# Misc_switches.net
KiCad netlist of a schematic drawn in Altium Designer
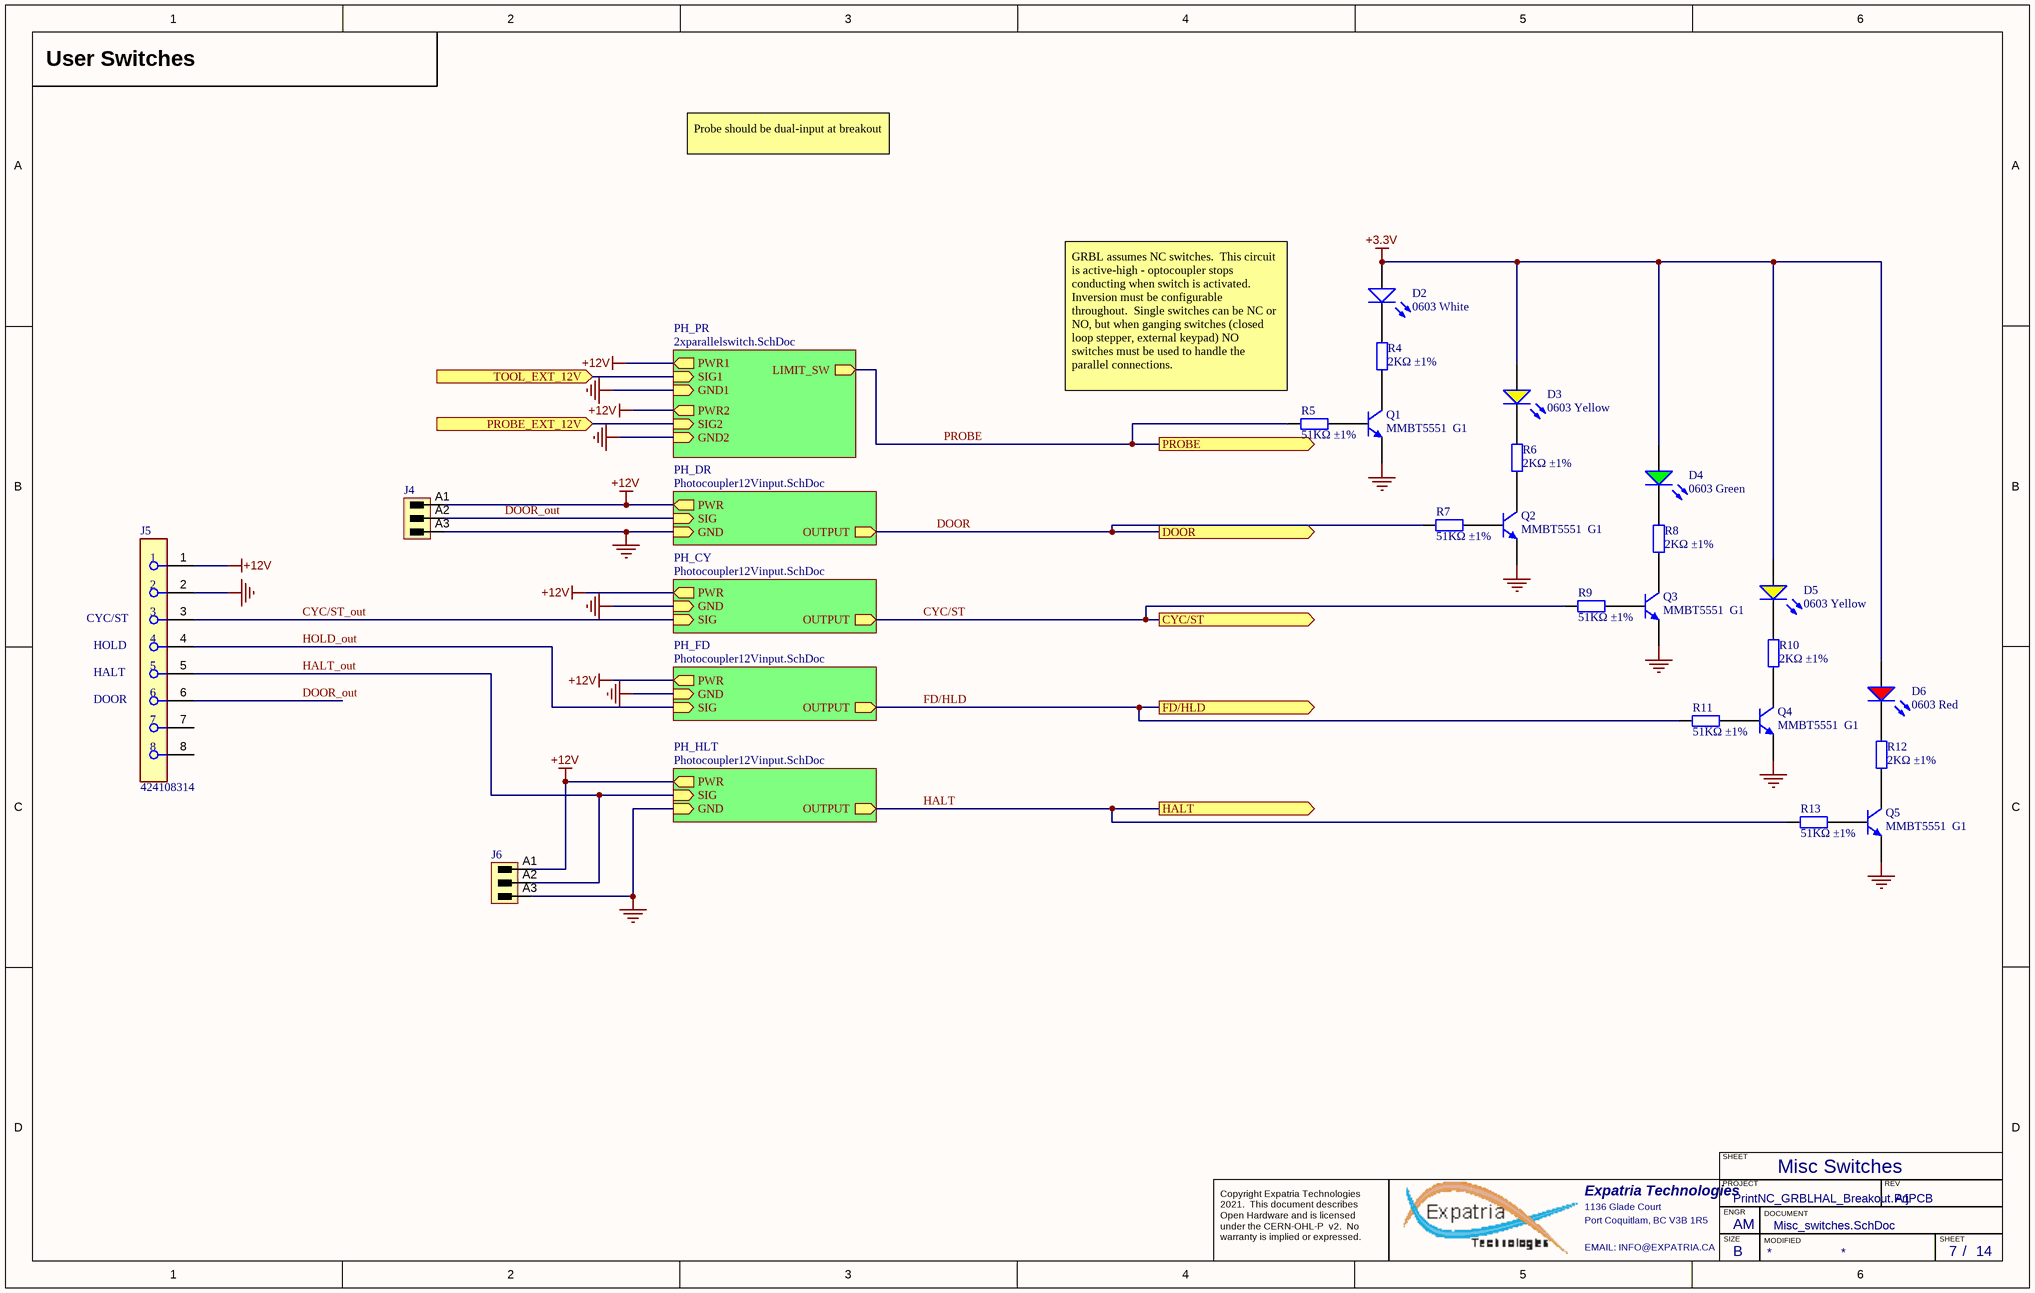
[diagram p0: Misc_switches.SchDoc]

(export (version "E")
  (design (tool "Eeschema 10.0.6"))
  (components
    (comp (ref "D2")
      (value "0603 White")
      (footprint "0603_LED_S1")
      (description "LED")
      (libsource (lib "LED") (part "0603 LED White"))
    )
    (comp (ref "D3")
      (value "0603 Yellow")
      (footprint "0603_LED_S1")
      (description "LED")
      (libsource (lib "LED") (part "0603 LED Yellow"))
    )
    (comp (ref "D4")
      (value "0603 Green")
      (footprint "0603_LED_S1")
      (description "LED")
      (libsource (lib "LED") (part "0603 LED Green"))
    )
    (comp (ref "D5")
      (value "0603 Yellow")
      (footprint "0603_LED_S1")
      (description "LED")
      (libsource (lib "LED") (part "0603 LED Yellow"))
    )
    (comp (ref "D6")
      (value "0603 Red")
      (footprint "0603_LED_S1")
      (description "LED")
      (libsource (lib "LED") (part "0603 LED Red"))
    )
    (comp (ref "J4")
      (value "~")
      (footprint "SL_3_50_180G_03")
      (fields
        (field (name "PARTNUMBER") "WJ15EDGVC-3.5-3P")
        (field (name "MANUFACTURER") "Ningbo Kangnex Elec")
      )
      (libsource (lib "PrintNC_GRBLHAL_Breakout") (part "Header_Male_03_1x03"))
    )
    (comp (ref "J5")
      (value "424108314")
      (footprint "FP-5555799-1-MFG")
      (description "CONN MOD JACK 8P8C VERT UNSHLD")
      (libsource (lib "PrintNC_GRBLHAL_Breakout") (part "a32a9c29f5c2290c50060dfb8ad7212"))
    )
    (comp (ref "J6")
      (value "~")
      (footprint "SL_3_50_180G_03")
      (fields
        (field (name "PARTNUMBER") "WJ15EDGVC-3.5-3P")
        (field (name "MANUFACTURER") "Ningbo Kangnex Elec")
      )
      (libsource (lib "PrintNC_GRBLHAL_Breakout") (part "Header_Male_03_1x03"))
    )
    (comp (ref "Q1")
      (value "MMBT5551  G1")
      (footprint "SOT-23(SOT-23-3)")
      (description "三极管")
      (libsource (lib "PrintNC_GRBLHAL_Breakout") (part "SOT-23 MMBT5551  G1"))
    )
    (comp (ref "Q2")
      (value "MMBT5551  G1")
      (footprint "SOT-23(SOT-23-3)")
      (description "三极管")
      (libsource (lib "PrintNC_GRBLHAL_Breakout") (part "SOT-23 MMBT5551  G1"))
    )
    (comp (ref "Q3")
      (value "MMBT5551  G1")
      (footprint "SOT-23(SOT-23-3)")
      (description "三极管")
      (libsource (lib "PrintNC_GRBLHAL_Breakout") (part "SOT-23 MMBT5551  G1"))
    )
    (comp (ref "Q4")
      (value "MMBT5551  G1")
      (footprint "SOT-23(SOT-23-3)")
      (description "三极管")
      (libsource (lib "PrintNC_GRBLHAL_Breakout") (part "SOT-23 MMBT5551  G1"))
    )
    (comp (ref "Q5")
      (value "MMBT5551  G1")
      (footprint "SOT-23(SOT-23-3)")
      (description "三极管")
      (libsource (lib "PrintNC_GRBLHAL_Breakout") (part "SOT-23 MMBT5551  G1"))
    )
    (comp (ref "R4")
      (value "2KΩ ±1%")
      (footprint "0402_R")
      (description "Chip resistor")
      (fields (field (name "MANUFACTURER") "Uniroyal Elec") (field (name "PARTNUMBER") "0402WGF2001TCE"))
      (libsource (lib "PrintNC_GRBLHAL_Breakout") (part "0402 2K (2001) 1%"))
    )
    (comp (ref "R5")
      (value "51KΩ ±1%")
      (footprint "0402_R")
      (description "Chip resistor")
      (fields (field (name "MANUFACTURER") "Uniroyal Elec") (field (name "PARTNUMBER") "0402WGF5102TCE"))
      (libsource (lib "RES") (part "0402 51K (5102) 1%"))
    )
    (comp (ref "R6")
      (value "2KΩ ±1%")
      (footprint "0402_R")
      (description "Chip resistor")
      (fields (field (name "MANUFACTURER") "Uniroyal Elec") (field (name "PARTNUMBER") "0402WGF2001TCE"))
      (libsource (lib "PrintNC_GRBLHAL_Breakout") (part "0402 2K (2001) 1%"))
    )
    (comp (ref "R7")
      (value "51KΩ ±1%")
      (footprint "0402_R")
      (description "Chip resistor")
      (fields (field (name "MANUFACTURER") "Uniroyal Elec") (field (name "PARTNUMBER") "0402WGF5102TCE"))
      (libsource (lib "RES") (part "0402 51K (5102) 1%"))
    )
    (comp (ref "R8")
      (value "2KΩ ±1%")
      (footprint "0402_R")
      (description "Chip resistor")
      (fields (field (name "MANUFACTURER") "Uniroyal Elec") (field (name "PARTNUMBER") "0402WGF2001TCE"))
      (libsource (lib "PrintNC_GRBLHAL_Breakout") (part "0402 2K (2001) 1%"))
    )
    (comp (ref "R9")
      (value "51KΩ ±1%")
      (footprint "0402_R")
      (description "Chip resistor")
      (fields (field (name "MANUFACTURER") "Uniroyal Elec") (field (name "PARTNUMBER") "0402WGF5102TCE"))
      (libsource (lib "RES") (part "0402 51K (5102) 1%"))
    )
    (comp (ref "R10")
      (value "2KΩ ±1%")
      (footprint "0402_R")
      (description "Chip resistor")
      (fields (field (name "MANUFACTURER") "Uniroyal Elec") (field (name "PARTNUMBER") "0402WGF2001TCE"))
      (libsource (lib "PrintNC_GRBLHAL_Breakout") (part "0402 2K (2001) 1%"))
    )
    (comp (ref "R11")
      (value "51KΩ ±1%")
      (footprint "0402_R")
      (description "Chip resistor")
      (fields (field (name "MANUFACTURER") "Uniroyal Elec") (field (name "PARTNUMBER") "0402WGF5102TCE"))
      (libsource (lib "RES") (part "0402 51K (5102) 1%"))
    )
    (comp (ref "R12")
      (value "2KΩ ±1%")
      (footprint "0402_R")
      (description "Chip resistor")
      (fields (field (name "MANUFACTURER") "Uniroyal Elec") (field (name "PARTNUMBER") "0402WGF2001TCE"))
      (libsource (lib "PrintNC_GRBLHAL_Breakout") (part "0402 2K (2001) 1%"))
    )
    (comp (ref "R13")
      (value "51KΩ ±1%")
      (footprint "0402_R")
      (description "Chip resistor")
      (fields (field (name "MANUFACTURER") "Uniroyal Elec") (field (name "PARTNUMBER") "0402WGF5102TCE"))
      (libsource (lib "RES") (part "0402 51K (5102) 1%"))
    )
  )
  (nets
    (net (code "1") (name "+3.3V") (class "Default")
      (node (ref "D2") (pin "A") (pinfunction "A_A") (pintype "passive"))
      (node (ref "D3") (pin "A") (pinfunction "A_A") (pintype "passive"))
      (node (ref "D4") (pin "A") (pinfunction "A_A") (pintype "passive"))
      (node (ref "D5") (pin "A") (pinfunction "A_A") (pintype "passive"))
      (node (ref "D6") (pin "A") (pinfunction "A_A") (pintype "passive"))
    )
    (net (code "2") (name "+12V") (class "Default")
      (node (ref "J4") (pin "A1") (pinfunction "A1_A1") (pintype "passive"))
      (node (ref "J5") (pin "1") (pinfunction "1_1") (pintype "passive"))
      (node (ref "J6") (pin "A1") (pinfunction "A1_A1") (pintype "passive"))
    )
    (net (code "3") (name "/CYC{slash}ST") (class "Default")
      (node (ref "R9") (pin "1") (pinfunction "1_1") (pintype "passive"))
    )
    (net (code "4") (name "/CYC{slash}ST_out") (class "Default")
      (node (ref "J5") (pin "3") (pinfunction "3_3") (pintype "passive"))
    )
    (net (code "5") (name "/DOOR") (class "Default")
      (node (ref "R7") (pin "1") (pinfunction "1_1") (pintype "passive"))
    )
    (net (code "6") (name "/DOOR_out") (class "Default")
      (node (ref "J4") (pin "A2") (pinfunction "A2_A2") (pintype "passive"))
      (node (ref "J5") (pin "6") (pinfunction "6_6") (pintype "passive"))
    )
    (net (code "7") (name "/FD{slash}HLD") (class "Default")
      (node (ref "R11") (pin "1") (pinfunction "1_1") (pintype "passive"))
    )
    (net (code "8") (name "/HALT") (class "Default")
      (node (ref "R13") (pin "1") (pinfunction "1_1") (pintype "passive"))
    )
    (net (code "9") (name "/HALT_out") (class "Default")
      (node (ref "J5") (pin "5") (pinfunction "5_5") (pintype "passive"))
      (node (ref "J6") (pin "A2") (pinfunction "A2_A2") (pintype "passive"))
    )
    (net (code "10") (name "/HOLD_out") (class "Default")
      (node (ref "J5") (pin "4") (pinfunction "4_4") (pintype "passive"))
    )
    (net (code "11") (name "/PROBE") (class "Default")
      (node (ref "R5") (pin "1") (pinfunction "1_1") (pintype "passive"))
    )
    (net (code "14") (name "GND") (class "Default")
      (node (ref "J4") (pin "A3") (pinfunction "A3_A3") (pintype "passive"))
      (node (ref "J5") (pin "2") (pinfunction "2_2") (pintype "passive"))
      (node (ref "J6") (pin "A3") (pinfunction "A3_A3") (pintype "passive"))
      (node (ref "Q1") (pin "2") (pinfunction "E_2") (pintype "passive"))
      (node (ref "Q2") (pin "2") (pinfunction "E_2") (pintype "passive"))
      (node (ref "Q3") (pin "2") (pinfunction "E_2") (pintype "passive"))
      (node (ref "Q4") (pin "2") (pinfunction "E_2") (pintype "passive"))
      (node (ref "Q5") (pin "2") (pinfunction "E_2") (pintype "passive"))
    )
    (net (code "15") (name "Net-(D2-PadK)") (class "Default")
      (node (ref "D2") (pin "K") (pinfunction "K_K") (pintype "passive"))
      (node (ref "R4") (pin "1") (pinfunction "1_1") (pintype "passive"))
    )
    (net (code "16") (name "Net-(D3-PadK)") (class "Default")
      (node (ref "D3") (pin "K") (pinfunction "K_K") (pintype "passive"))
      (node (ref "R6") (pin "1") (pinfunction "1_1") (pintype "passive"))
    )
    (net (code "17") (name "Net-(D4-PadK)") (class "Default")
      (node (ref "D4") (pin "K") (pinfunction "K_K") (pintype "passive"))
      (node (ref "R8") (pin "1") (pinfunction "1_1") (pintype "passive"))
    )
    (net (code "18") (name "Net-(D5-PadK)") (class "Default")
      (node (ref "D5") (pin "K") (pinfunction "K_K") (pintype "passive"))
      (node (ref "R10") (pin "1") (pinfunction "1_1") (pintype "passive"))
    )
    (net (code "19") (name "Net-(D6-PadK)") (class "Default")
      (node (ref "D6") (pin "K") (pinfunction "K_K") (pintype "passive"))
      (node (ref "R12") (pin "1") (pinfunction "1_1") (pintype "passive"))
    )
    (net (code "20") (name "Net-(Q1-B)") (class "Default")
      (node (ref "Q1") (pin "1") (pinfunction "B_1") (pintype "passive"))
      (node (ref "R5") (pin "2") (pinfunction "2_2") (pintype "passive"))
    )
    (net (code "21") (name "Net-(Q1-C)") (class "Default")
      (node (ref "Q1") (pin "3") (pinfunction "C_3") (pintype "passive"))
      (node (ref "R4") (pin "2") (pinfunction "2_2") (pintype "passive"))
    )
    (net (code "22") (name "Net-(Q2-B)") (class "Default")
      (node (ref "Q2") (pin "1") (pinfunction "B_1") (pintype "passive"))
      (node (ref "R7") (pin "2") (pinfunction "2_2") (pintype "passive"))
    )
    (net (code "23") (name "Net-(Q2-C)") (class "Default")
      (node (ref "Q2") (pin "3") (pinfunction "C_3") (pintype "passive"))
      (node (ref "R6") (pin "2") (pinfunction "2_2") (pintype "passive"))
    )
    (net (code "24") (name "Net-(Q3-B)") (class "Default")
      (node (ref "Q3") (pin "1") (pinfunction "B_1") (pintype "passive"))
      (node (ref "R9") (pin "2") (pinfunction "2_2") (pintype "passive"))
    )
    (net (code "25") (name "Net-(Q3-C)") (class "Default")
      (node (ref "Q3") (pin "3") (pinfunction "C_3") (pintype "passive"))
      (node (ref "R8") (pin "2") (pinfunction "2_2") (pintype "passive"))
    )
    (net (code "26") (name "Net-(Q4-B)") (class "Default")
      (node (ref "Q4") (pin "1") (pinfunction "B_1") (pintype "passive"))
      (node (ref "R11") (pin "2") (pinfunction "2_2") (pintype "passive"))
    )
    (net (code "27") (name "Net-(Q4-C)") (class "Default")
      (node (ref "Q4") (pin "3") (pinfunction "C_3") (pintype "passive"))
      (node (ref "R10") (pin "2") (pinfunction "2_2") (pintype "passive"))
    )
    (net (code "28") (name "Net-(Q5-B)") (class "Default")
      (node (ref "Q5") (pin "1") (pinfunction "B_1") (pintype "passive"))
      (node (ref "R13") (pin "2") (pinfunction "2_2") (pintype "passive"))
    )
    (net (code "29") (name "Net-(Q5-C)") (class "Default")
      (node (ref "Q5") (pin "3") (pinfunction "C_3") (pintype "passive"))
      (node (ref "R12") (pin "2") (pinfunction "2_2") (pintype "passive"))
    )
    (net (code "30") (name "unconnected-(J5-Pad7)") (class "Default")
      (node (ref "J5") (pin "7") (pinfunction "7_7") (pintype "passive"))
    )
    (net (code "31") (name "unconnected-(J5-Pad8)") (class "Default")
      (node (ref "J5") (pin "8") (pinfunction "8_8") (pintype "passive"))
    )
  )
)
